# Interface_Board_Top.net
KiCad netlist of a schematic drawn in Altium Designer
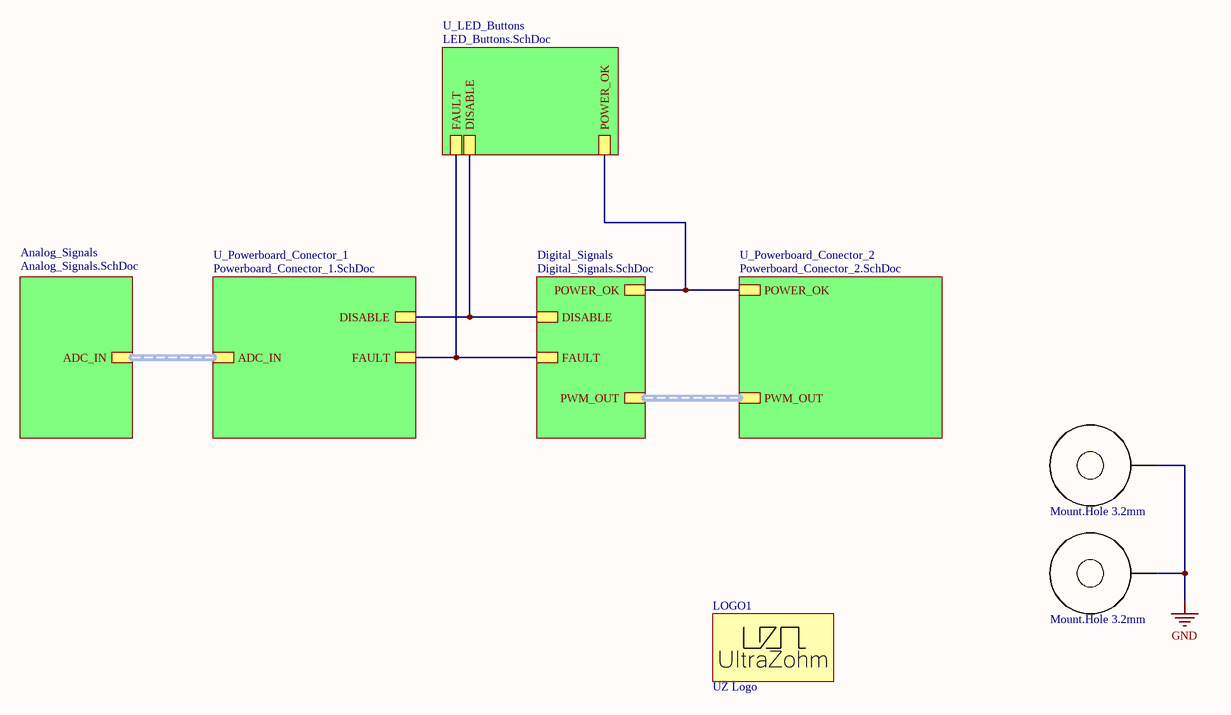
[diagram p0: Interface_Board_Top.SchDoc]

(export (version "E")
  (design (tool "Eeschema 10.0.6"))
  (components
    (comp (ref "H1")
      (value "Mount.Hole 3.2mm")
      (footprint "MHole3_2mm_No_Screw")
      (libsource (lib "connectors_testpoints") (part "MHole"))
    )
    (comp (ref "H2")
      (value "Mount.Hole 3.2mm")
      (footprint "MHole3_2mm_No_Screw")
      (libsource (lib "connectors_testpoints") (part "MHole"))
    )
    (comp (ref "LOGO1")
      (value "UZ Logo")
      (footprint "UZ_Logo_tiny")
      (description "UltraZohm Logo on PCB")
      (fields (field (name "CREATED") "Jan2021_Liegmann"))
      (libsource (lib "PCB_Logo") (part "UZ Logo"))
    )
  )
  (nets
    (net (code "6") (name "GND") (class "Default")
      (node (ref "H1") (pin "1") (pinfunction "1_1") (pintype "passive"))
      (node (ref "H2") (pin "1") (pinfunction "1_1") (pintype "passive"))
    )
  )
)
